# Buck_Converter_Schematic.net
KiCad netlist of a schematic drawn in Altium Designer
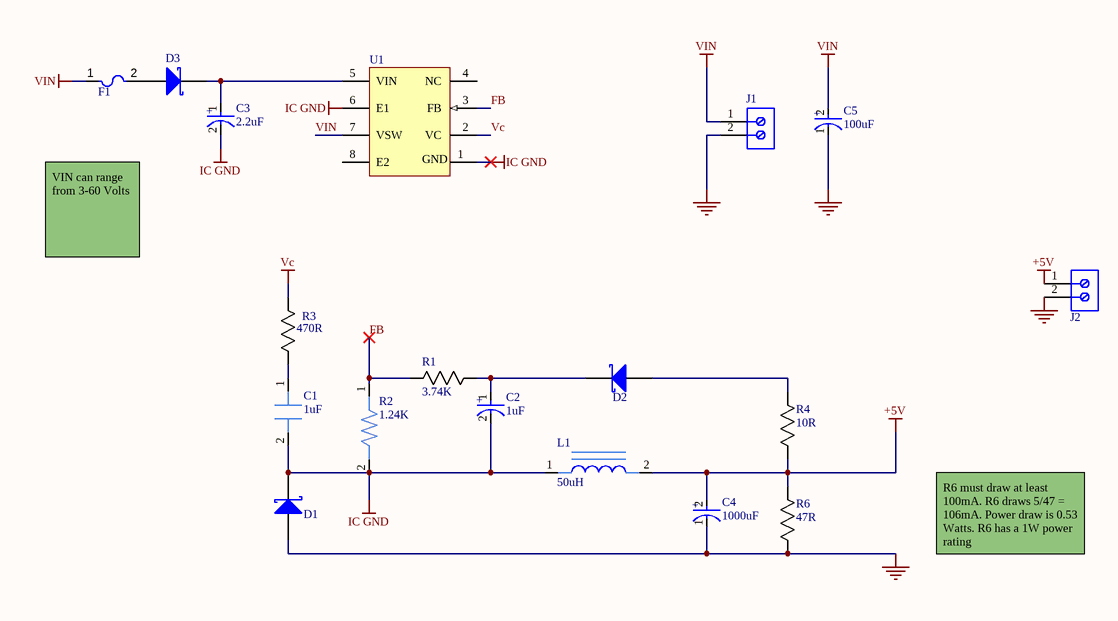
[diagram p0: Buck Converter Schematic.SchDoc]

(export (version "E")
  (design (tool "Eeschema 10.0.6"))
  (components
    (comp (ref "C1")
      (value "1uF")
      (footprint "C1210C105K5RACTU")
      (description "Ceramic Capacitor 1uF")
      (fields
        (field (name "MANUFACTURER") "KEMET")
        (field (name "MANUFACTURER PART NUMBER") "ESL105M100AC3AA")
      )
      (libsource (lib "Boost") (part "CL10B105KA8NNNC"))
    )
    (comp (ref "C2")
      (value "1uF")
      (footprint "Radial, Can")
      (description "1 µF 50 V Aluminum Electrolytic Capacitors Radial, Can 2000 Hrs @ 105°C")
      (fields (field (name "Comment") "860020672005"))
      (libsource (lib "NP_Schlib") (part "860020672005"))
    )
    (comp (ref "C3")
      (value "2.2uF")
      (footprint "Radial, Can")
      (description "2.2 µF 50 V Aluminum Electrolytic Capacitors Radial, Can 2000 Hrs @ 105°C")
      (fields (field (name "Comment") "860020672006"))
      (libsource (lib "NP_Schlib") (part "860020672006"))
    )
    (comp (ref "C4")
      (value "1000uF")
      (footprint "25PX1000MEFCT810X16")
      (fields
        (field (name "MANUFACTURER") "Rubycon")
        (field (name "MANUFACTURER PART NUMBER") "16ZLH1000MEFC10X16")
      )
      (libsource (lib "Boost") (part "16ZLH1000MEFC10X16"))
    )
    (comp (ref "C5")
      (value "100uF")
      (footprint "35ZLH100MEFC6.3X11")
      (description "CAP ALUM 100UF 20% 35V RADIAL")
      (fields (field (name "VOLTAGE") "35V") (field (name "TOLERANCE") "20%"))
      (libsource (lib "Boost") (part "a00bbbee19879c290e62620ae7e47b1"))
    )
    (comp (ref "D1")
      (value "BAT46W-7-F")
      (footprint "DIOD-SOD-123-2_V")
      (description "Surface Mount Schottky Barrier Diode, 100 V, -55 to 125 degC, 2-Pin SOD123, RoHS, Tape and Reel")
      (fields (field (name "MANUFACTURER") "Diodes Inc"))
      (libsource (lib "Buck Converter") (part "CMP-0303-00004-1"))
    )
    (comp (ref "D2")
      (value "BAT46W-7-F")
      (footprint "DIOD-SOD-123-2_V")
      (description "Surface Mount Schottky Barrier Diode, 100 V, -55 to 125 degC, 2-Pin SOD123, RoHS, Tape and Reel")
      (fields (field (name "MANUFACTURER") "Diodes Inc"))
      (libsource (lib "Buck Converter") (part "CMP-0303-00004-1"))
    )
    (comp (ref "D3")
      (value "BAT46W-7-F")
      (footprint "DIOD-SOD-123-2_V")
      (description "Surface Mount Schottky Barrier Diode, 100 V, -55 to 125 degC, 2-Pin SOD123, RoHS, Tape and Reel")
      (fields (field (name "MANUFACTURER") "Diodes Inc"))
      (libsource (lib "Buck Converter") (part "CMP-0303-00004-1"))
    )
    (comp (ref "F1")
      (value "0ZCF0185FF2C")
      (footprint "2920 (7351 Metric), Concave")
      (description "Polymeric PTC Resettable Fuse 33V 1.85 A Ih Surface Mount 2920 (7351 Metric), Concave")
      (libsource (lib "NP_Schlib") (part "0ZCF0185FF2C"))
    )
    (comp (ref "J1")
      (value "691137710002")
      (footprint "691137710002")
      (libsource (lib "Altium Content Vault") (part "TBL - 1R - 02P - Screw"))
    )
    (comp (ref "J2")
      (value "691137710002")
      (footprint "691137710002")
      (libsource (lib "Altium Content Vault") (part "TBL - 1R - 02P - Screw"))
    )
    (comp (ref "L1")
      (value "50uH")
      (footprint "CTX50-1-52-R")
      (description "General Purpose Inductor, 50uH, 1 Element, Iron-Core")
      (fields
        (field (name "MANUFACTURER") "Eaton Cooper")
        (field (name "MANUFACTURER PART NUMBER") "CTX50-1-52-R")
      )
      (libsource (lib "Boost") (part "CTX50-1-52-R"))
    )
    (comp (ref "R1")
      (value "RMCF0805FT3K74")
      (footprint "0805")
      (description "3.74 kOhms ±1% 0.125W, 1/8W Chip Resistor 0805 (2012 Metric) Automotive AEC-Q200 Thick Film")
      (fields (field (name "RESISTANCE") "3.74K"))
      (libsource (lib "NP Altium Library") (part "RMCF0805FT3K74"))
    )
    (comp (ref "R2")
      (value "1.24K")
      (footprint "RC0805FR-071K24L")
      (description "Fixed Resistor, Metal Film, 0.25W, 1240ohm, 250V, 1% +/-Tol, -100,100ppm/Cel")
      (fields
        (field (name "MANUFACTURER") "Yageo")
        (field (name "MANUFACTURER PART NUMBER") "MFR-25FBF52-1K24")
      )
      (libsource (lib "Boost") (part "RC0805FR-071K24L"))
    )
    (comp (ref "R3")
      (value "RMCF0805FT470R")
      (footprint "0805")
      (description "470 Ohms ±1% 0.125W, 1/8W Chip Resistor 0805 (2012 Metric) Automotive AEC-Q200 Thick Film")
      (fields (field (name "RESISTANCE") "470R"))
      (libsource (lib "NP Altium Library") (part "RMCF0805FT470R"))
    )
    (comp (ref "R4")
      (value "RMCF0805JT10R0")
      (footprint "0805")
      (description "10 Ohms ±5% 0.125W, 1/8W Chip Resistor 0805 (2012 Metric) Automotive AEC-Q200 Thick Film")
      (fields (field (name "RESISTANCE") "10R"))
      (libsource (lib "NP Altium Library") (part "RMCF0805JT10R0"))
    )
    (comp (ref "R6")
      (value "LTR10EZPJ470")
      (footprint "0805")
      (fields (field (name "RESISTANCE") "47R"))
      (libsource (lib "NP Altium Library") (part "LTR10EZPJ470"))
    )
    (comp (ref "U1")
      (value "LT1172CN8#PBF")
      (footprint "LT1172CN8#PBF-ND")
      (description "100 kHz, 1.25 A, High Efficiency Switching Regulator, 8-pin DIP (N8-8), 0 to 100 degC, Pb-Free")
      (fields (field (name "MANUFACTURER") "Linear Technology"))
      (libsource (lib "Boost") (part "LT-LT1172-X8-8"))
    )
  )
  (nets
    (net (code "1") (name "+5V") (class "Default")
      (node (ref "C4") (pin "2") (pinfunction "A_2") (pintype "passive"))
      (node (ref "J2") (pin "1") (pinfunction "1_1") (pintype "passive"))
      (node (ref "L1") (pin "2") (pinfunction "2_2") (pintype "passive"))
      (node (ref "R4") (pin "1") (pinfunction "1_1") (pintype "passive"))
      (node (ref "R6") (pin "2") (pinfunction "2_2") (pintype "passive"))
    )
    (net (code "2") (name "/FB") (class "Default")
      (node (ref "R1") (pin "1") (pinfunction "1_1") (pintype "passive"))
      (node (ref "R2") (pin "1") (pinfunction "1_1") (pintype "passive"))
      (node (ref "U1") (pin "3") (pinfunction "FB_3") (pintype "input"))
    )
    (net (code "3") (name "GND") (class "Default")
      (node (ref "C4") (pin "1") (pinfunction "C_1") (pintype "passive"))
      (node (ref "C5") (pin "1") (pinfunction "C_1") (pintype "passive"))
      (node (ref "D1") (pin "1") (pinfunction "A_1") (pintype "passive"))
      (node (ref "J1") (pin "2") (pinfunction "2_2") (pintype "passive"))
      (node (ref "J2") (pin "2") (pinfunction "2_2") (pintype "passive"))
      (node (ref "R6") (pin "1") (pinfunction "1_1") (pintype "passive"))
    )
    (net (code "4") (name "IC GND") (class "Default")
      (node (ref "C1") (pin "2") (pinfunction "2_2") (pintype "passive"))
      (node (ref "C2") (pin "2") (pinfunction "C_2") (pintype "passive"))
      (node (ref "C3") (pin "2") (pinfunction "C_2") (pintype "passive"))
      (node (ref "D1") (pin "2") (pinfunction "K_2") (pintype "passive"))
      (node (ref "L1") (pin "1") (pinfunction "1_1") (pintype "passive"))
      (node (ref "R2") (pin "2") (pinfunction "2_2") (pintype "passive"))
      (node (ref "U1") (pin "6") (pinfunction "E1_6") (pintype "passive"))
    )
    (net (code "5") (name "Net-(C1-Pad1)") (class "Default")
      (node (ref "C1") (pin "1") (pinfunction "1_1") (pintype "passive"))
      (node (ref "R3") (pin "1") (pinfunction "1_1") (pintype "passive"))
    )
    (net (code "6") (name "Net-(C2-A)") (class "Default")
      (node (ref "C2") (pin "1") (pinfunction "A_1") (pintype "passive"))
      (node (ref "D2") (pin "2") (pinfunction "K_2") (pintype "passive"))
      (node (ref "R1") (pin "2") (pinfunction "2_2") (pintype "passive"))
    )
    (net (code "7") (name "Net-(C3-A)") (class "Default")
      (node (ref "C3") (pin "1") (pinfunction "A_1") (pintype "passive"))
      (node (ref "D3") (pin "2") (pinfunction "K_2") (pintype "passive"))
      (node (ref "U1") (pin "5") (pinfunction "VIN_5") (pintype "power_in"))
    )
    (net (code "8") (name "Net-(D2-A)") (class "Default")
      (node (ref "D2") (pin "1") (pinfunction "A_1") (pintype "passive"))
      (node (ref "R4") (pin "2") (pinfunction "2_2") (pintype "passive"))
    )
    (net (code "9") (name "Net-(D3-A)") (class "Default")
      (node (ref "D3") (pin "1") (pinfunction "A_1") (pintype "passive"))
      (node (ref "F1") (pin "2") (pinfunction "2_2") (pintype "passive"))
    )
    (net (code "10") (name "VIN") (class "Default")
      (node (ref "C5") (pin "2") (pinfunction "A_2") (pintype "passive"))
      (node (ref "F1") (pin "1") (pinfunction "1_1") (pintype "passive"))
      (node (ref "J1") (pin "1") (pinfunction "1_1") (pintype "passive"))
      (node (ref "U1") (pin "7") (pinfunction "VSW_7") (pintype "power_in"))
    )
    (net (code "11") (name "Vc") (class "Default")
      (node (ref "R3") (pin "2") (pinfunction "2_2") (pintype "passive"))
      (node (ref "U1") (pin "2") (pinfunction "VC_2") (pintype "passive"))
    )
    (net (code "12") (name "unconnected-(U1-E2-Pad8)") (class "Default")
      (node (ref "U1") (pin "8") (pinfunction "E2_8") (pintype "passive"))
    )
    (net (code "13") (name "unconnected-(U1-GND-Pad1)") (class "Default")
      (node (ref "U1") (pin "1") (pinfunction "GND_1") (pintype "power_in"))
    )
    (net (code "14") (name "unconnected-(U1-NC-Pad4)") (class "Default")
      (node (ref "U1") (pin "4") (pinfunction "NC_4") (pintype "passive"))
    )
  )
)
